# edition4-mainpart_1.net
KiCad netlist of a schematic drawn in EAGLE
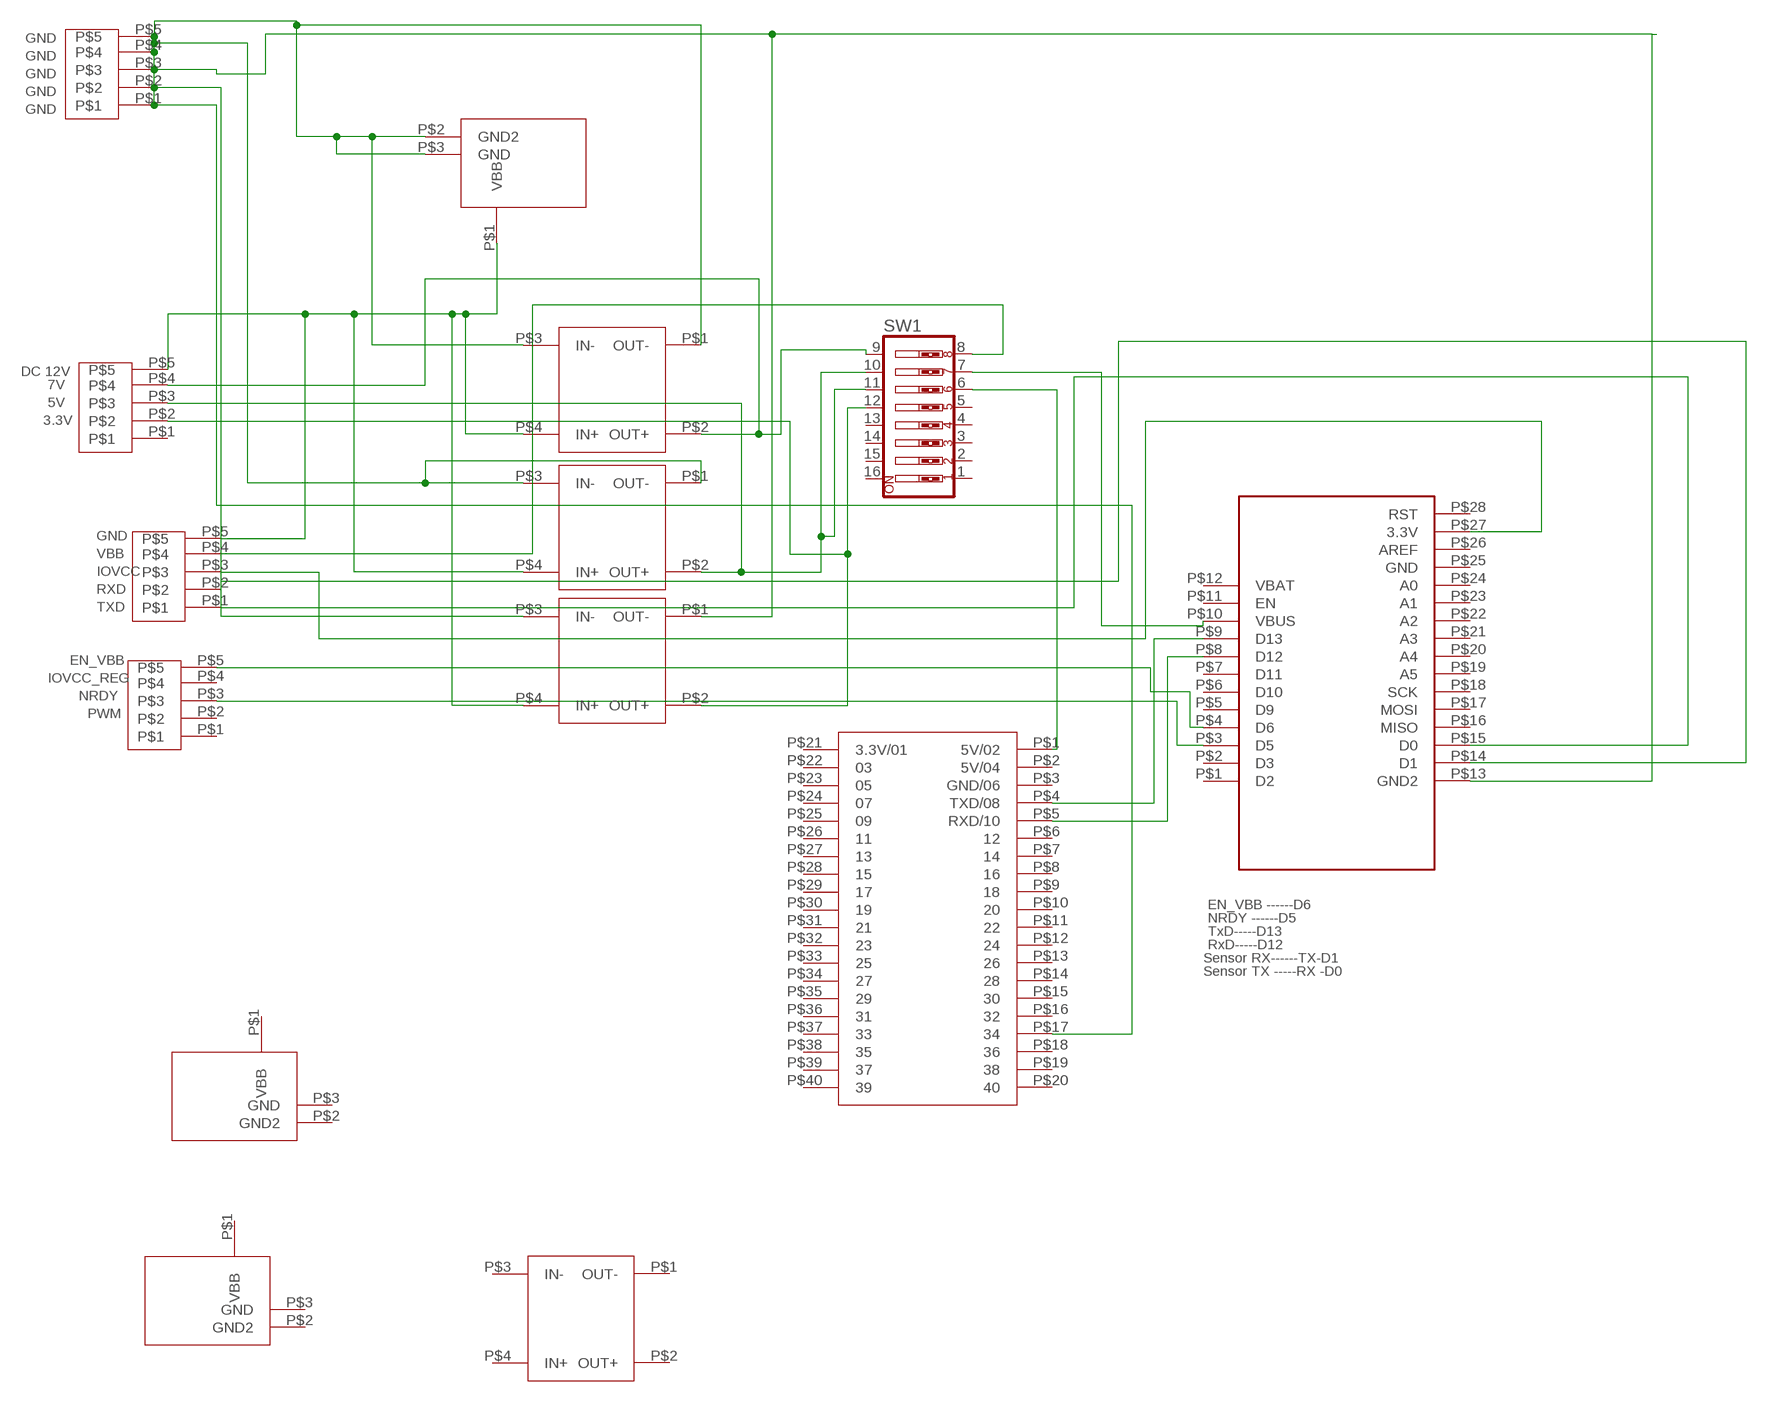
[diagram p0: schematic, sheet 1]

(export (version "E")
  (design (tool "Eeschema 10.0.6"))
  (components
    (comp (ref "SW1")
      (value "SW_DIP-8")
      (footprint "eagle-import:EDG-08")
      (libsource (lib "eagle-import") (part "SW_DIP-8"))
    )
    (comp (ref "U$1")
      (value "PIN")
      (footprint "eagle-import:PIN")
      (libsource (lib "eagle-import") (part "PIN"))
    )
    (comp (ref "U$2")
      (value "PIN")
      (footprint "eagle-import:PIN")
      (libsource (lib "eagle-import") (part "PIN"))
    )
    (comp (ref "U$3")
      (value "POWER")
      (footprint "eagle-import:POWERIN")
      (libsource (lib "eagle-import") (part "POWER"))
    )
    (comp (ref "U$4")
      (value "POWER")
      (footprint "eagle-import:POWERIN")
      (libsource (lib "eagle-import") (part "POWER"))
    )
    (comp (ref "U$5")
      (value "POWER")
      (footprint "eagle-import:POWERIN")
      (libsource (lib "eagle-import") (part "POWER"))
    )
    (comp (ref "U$6")
      (value "MH-MINI-360")
      (footprint "eagle-import:MH-MINI-360")
      (libsource (lib "eagle-import") (part "MH-MINI-360"))
    )
    (comp (ref "U$7")
      (value "MH-MINI-360")
      (footprint "eagle-import:MH-MINI-360")
      (libsource (lib "eagle-import") (part "MH-MINI-360"))
    )
    (comp (ref "U$8")
      (value "MH-MINI-360")
      (footprint "eagle-import:MH-MINI-360")
      (libsource (lib "eagle-import") (part "MH-MINI-360"))
    )
    (comp (ref "U$9")
      (value "MH-MINI-360")
      (footprint "eagle-import:MH-MINI-360")
      (libsource (lib "eagle-import") (part "MH-MINI-360"))
    )
    (comp (ref "U$10")
      (value "FEATHER")
      (footprint "eagle-import:FEATHER")
      (libsource (lib "eagle-import") (part "FEATHER"))
    )
    (comp (ref "U$11")
      (value "RASPBERRYPI")
      (footprint "eagle-import:RASPBERRYPI")
      (libsource (lib "eagle-import") (part "RASPBERRYPI"))
    )
    (comp (ref "U$12")
      (value "PIN")
      (footprint "eagle-import:PIN")
      (libsource (lib "eagle-import") (part "PIN"))
    )
    (comp (ref "U$13")
      (value "PIN")
      (footprint "eagle-import:PIN")
      (libsource (lib "eagle-import") (part "PIN"))
    )
  )
  (nets
    (net (code "1") (name "Net-(SW1-Pad8)") (class "Default")
      (node (ref "SW1") (pin "8") (pinfunction "8_8") (pintype "passive"))
      (node (ref "U$1") (pin "P$4") (pinfunction "P$4_P$4") (pintype "bidirectional"))
    )
    (net (code "2") (name "Net-(U$3-VBB)") (class "Default")
      (node (ref "U$1") (pin "P$5") (pinfunction "P$5_P$5") (pintype "bidirectional"))
      (node (ref "U$12") (pin "P$5") (pinfunction "P$5_P$5") (pintype "bidirectional"))
      (node (ref "U$3") (pin "P$1") (pinfunction "VBB_P$1") (pintype "bidirectional"))
      (node (ref "U$6") (pin "P$4") (pinfunction "IN+_P$4") (pintype "bidirectional"))
      (node (ref "U$8") (pin "P$4") (pinfunction "IN+_P$4") (pintype "bidirectional"))
      (node (ref "U$9") (pin "P$4") (pinfunction "IN+_P$4") (pintype "bidirectional"))
    )
    (net (code "3") (name "Net-(U$6-OUT+)") (class "Default")
      (node (ref "SW1") (pin "9") (pinfunction "9_9") (pintype "passive"))
      (node (ref "U$12") (pin "P$4") (pinfunction "P$4_P$4") (pintype "bidirectional"))
      (node (ref "U$6") (pin "P$2") (pinfunction "OUT+_P$2") (pintype "bidirectional"))
    )
    (net (code "4") (name "Net-(U$8-OUT+)") (class "Default")
      (node (ref "SW1") (pin "12") (pinfunction "12_12") (pintype "passive"))
      (node (ref "U$12") (pin "P$2") (pinfunction "P$2_P$2") (pintype "bidirectional"))
      (node (ref "U$8") (pin "P$2") (pinfunction "OUT+_P$2") (pintype "bidirectional"))
    )
    (net (code "5") (name "Net-(U$9-OUT+)") (class "Default")
      (node (ref "SW1") (pin "10") (pinfunction "10_10") (pintype "passive"))
      (node (ref "SW1") (pin "11") (pinfunction "11_11") (pintype "passive"))
      (node (ref "U$12") (pin "P$3") (pinfunction "P$3_P$3") (pintype "bidirectional"))
      (node (ref "U$9") (pin "P$2") (pinfunction "OUT+_P$2") (pintype "bidirectional"))
    )
    (net (code "6") (name "Net-(U$10-3.3V)") (class "Default")
      (node (ref "U$1") (pin "P$3") (pinfunction "P$3_P$3") (pintype "bidirectional"))
      (node (ref "U$10") (pin "P$27") (pinfunction "3.3V_P$27") (pintype "bidirectional"))
    )
    (net (code "7") (name "Net-(U$10-D0)") (class "Default")
      (node (ref "U$1") (pin "P$1") (pinfunction "P$1_P$1") (pintype "bidirectional"))
      (node (ref "U$10") (pin "P$15") (pinfunction "D0_P$15") (pintype "bidirectional"))
    )
    (net (code "8") (name "Net-(U$10-D1)") (class "Default")
      (node (ref "U$1") (pin "P$2") (pinfunction "P$2_P$2") (pintype "bidirectional"))
      (node (ref "U$10") (pin "P$14") (pinfunction "D1_P$14") (pintype "bidirectional"))
    )
    (net (code "9") (name "Net-(U$10-D5)") (class "Default")
      (node (ref "U$10") (pin "P$3") (pinfunction "D5_P$3") (pintype "bidirectional"))
      (node (ref "U$2") (pin "P$3") (pinfunction "P$3_P$3") (pintype "bidirectional"))
    )
    (net (code "10") (name "Net-(U$10-D6)") (class "Default")
      (node (ref "U$10") (pin "P$4") (pinfunction "D6_P$4") (pintype "bidirectional"))
      (node (ref "U$2") (pin "P$5") (pinfunction "P$5_P$5") (pintype "bidirectional"))
    )
    (net (code "11") (name "Net-(U$10-D12)") (class "Default")
      (node (ref "U$10") (pin "P$8") (pinfunction "D12_P$8") (pintype "bidirectional"))
      (node (ref "U$11") (pin "P$5") (pinfunction "RXD/10_P$5") (pintype "bidirectional"))
    )
    (net (code "12") (name "Net-(U$10-D13)") (class "Default")
      (node (ref "U$10") (pin "P$9") (pinfunction "D13_P$9") (pintype "bidirectional"))
      (node (ref "U$11") (pin "P$4") (pinfunction "TXD/08_P$4") (pintype "bidirectional"))
    )
    (net (code "13") (name "Net-(U$10-GND2)") (class "Default")
      (node (ref "U$10") (pin "P$13") (pinfunction "GND2_P$13") (pintype "bidirectional"))
      (node (ref "U$11") (pin "P$17") (pinfunction "34_P$17") (pintype "bidirectional"))
      (node (ref "U$13") (pin "P$1") (pinfunction "P$1_P$1") (pintype "bidirectional"))
      (node (ref "U$13") (pin "P$2") (pinfunction "P$2_P$2") (pintype "bidirectional"))
      (node (ref "U$13") (pin "P$3") (pinfunction "P$3_P$3") (pintype "bidirectional"))
      (node (ref "U$13") (pin "P$4") (pinfunction "P$4_P$4") (pintype "bidirectional"))
      (node (ref "U$13") (pin "P$5") (pinfunction "P$5_P$5") (pintype "bidirectional"))
      (node (ref "U$3") (pin "P$2") (pinfunction "GND2_P$2") (pintype "bidirectional"))
      (node (ref "U$3") (pin "P$3") (pinfunction "GND_P$3") (pintype "bidirectional"))
      (node (ref "U$6") (pin "P$1") (pinfunction "OUT-_P$1") (pintype "bidirectional"))
      (node (ref "U$6") (pin "P$3") (pinfunction "IN-_P$3") (pintype "bidirectional"))
      (node (ref "U$8") (pin "P$1") (pinfunction "OUT-_P$1") (pintype "bidirectional"))
      (node (ref "U$8") (pin "P$3") (pinfunction "IN-_P$3") (pintype "bidirectional"))
      (node (ref "U$9") (pin "P$1") (pinfunction "OUT-_P$1") (pintype "bidirectional"))
      (node (ref "U$9") (pin "P$3") (pinfunction "IN-_P$3") (pintype "bidirectional"))
    )
    (net (code "14") (name "Net-(U$10-VBUS)") (class "Default")
      (node (ref "SW1") (pin "7") (pinfunction "7_7") (pintype "passive"))
      (node (ref "U$10") (pin "P$10") (pinfunction "VBUS_P$10") (pintype "bidirectional"))
    )
    (net (code "15") (name "Net-(U$11-5V{slash}02)") (class "Default")
      (node (ref "SW1") (pin "6") (pinfunction "6_6") (pintype "passive"))
      (node (ref "U$11") (pin "P$1") (pinfunction "5V/02_P$1") (pintype "bidirectional"))
    )
    (net (code "16") (name "unconnected-(SW1-Pad1)") (class "Default")
      (node (ref "SW1") (pin "1") (pinfunction "1_1") (pintype "passive"))
    )
    (net (code "17") (name "unconnected-(SW1-Pad2)") (class "Default")
      (node (ref "SW1") (pin "2") (pinfunction "2_2") (pintype "passive"))
    )
    (net (code "18") (name "unconnected-(SW1-Pad3)") (class "Default")
      (node (ref "SW1") (pin "3") (pinfunction "3_3") (pintype "passive"))
    )
    (net (code "19") (name "unconnected-(SW1-Pad4)") (class "Default")
      (node (ref "SW1") (pin "4") (pinfunction "4_4") (pintype "passive"))
    )
    (net (code "20") (name "unconnected-(SW1-Pad5)") (class "Default")
      (node (ref "SW1") (pin "5") (pinfunction "5_5") (pintype "passive"))
    )
    (net (code "21") (name "unconnected-(SW1-Pad13)") (class "Default")
      (node (ref "SW1") (pin "13") (pinfunction "13_13") (pintype "passive"))
    )
    (net (code "22") (name "unconnected-(SW1-Pad14)") (class "Default")
      (node (ref "SW1") (pin "14") (pinfunction "14_14") (pintype "passive"))
    )
    (net (code "23") (name "unconnected-(SW1-Pad15)") (class "Default")
      (node (ref "SW1") (pin "15") (pinfunction "15_15") (pintype "passive"))
    )
    (net (code "24") (name "unconnected-(SW1-Pad16)") (class "Default")
      (node (ref "SW1") (pin "16") (pinfunction "16_16") (pintype "passive"))
    )
    (net (code "25") (name "unconnected-(U$2-PadP$1)") (class "Default")
      (node (ref "U$2") (pin "P$1") (pinfunction "P$1_P$1") (pintype "bidirectional"))
    )
    (net (code "26") (name "unconnected-(U$2-PadP$2)") (class "Default")
      (node (ref "U$2") (pin "P$2") (pinfunction "P$2_P$2") (pintype "bidirectional"))
    )
    (net (code "27") (name "unconnected-(U$2-PadP$4)") (class "Default")
      (node (ref "U$2") (pin "P$4") (pinfunction "P$4_P$4") (pintype "bidirectional"))
    )
    (net (code "28") (name "unconnected-(U$4-GND-PadP$3)") (class "Default")
      (node (ref "U$4") (pin "P$3") (pinfunction "GND_P$3") (pintype "bidirectional"))
    )
    (net (code "29") (name "unconnected-(U$4-GND2-PadP$2)") (class "Default")
      (node (ref "U$4") (pin "P$2") (pinfunction "GND2_P$2") (pintype "bidirectional"))
    )
    (net (code "30") (name "unconnected-(U$4-VBB-PadP$1)") (class "Default")
      (node (ref "U$4") (pin "P$1") (pinfunction "VBB_P$1") (pintype "bidirectional"))
    )
    (net (code "31") (name "unconnected-(U$5-GND-PadP$3)") (class "Default")
      (node (ref "U$5") (pin "P$3") (pinfunction "GND_P$3") (pintype "bidirectional"))
    )
    (net (code "32") (name "unconnected-(U$5-GND2-PadP$2)") (class "Default")
      (node (ref "U$5") (pin "P$2") (pinfunction "GND2_P$2") (pintype "bidirectional"))
    )
    (net (code "33") (name "unconnected-(U$5-VBB-PadP$1)") (class "Default")
      (node (ref "U$5") (pin "P$1") (pinfunction "VBB_P$1") (pintype "bidirectional"))
    )
    (net (code "34") (name "unconnected-(U$7-IN+-PadP$4)") (class "Default")
      (node (ref "U$7") (pin "P$4") (pinfunction "IN+_P$4") (pintype "bidirectional"))
    )
    (net (code "35") (name "unconnected-(U$7-IN--PadP$3)") (class "Default")
      (node (ref "U$7") (pin "P$3") (pinfunction "IN-_P$3") (pintype "bidirectional"))
    )
    (net (code "36") (name "unconnected-(U$7-OUT+-PadP$2)") (class "Default")
      (node (ref "U$7") (pin "P$2") (pinfunction "OUT+_P$2") (pintype "bidirectional"))
    )
    (net (code "37") (name "unconnected-(U$7-OUT--PadP$1)") (class "Default")
      (node (ref "U$7") (pin "P$1") (pinfunction "OUT-_P$1") (pintype "bidirectional"))
    )
    (net (code "38") (name "unconnected-(U$10-A0-PadP$24)") (class "Default")
      (node (ref "U$10") (pin "P$24") (pinfunction "A0_P$24") (pintype "bidirectional"))
    )
    (net (code "39") (name "unconnected-(U$10-A1-PadP$23)") (class "Default")
      (node (ref "U$10") (pin "P$23") (pinfunction "A1_P$23") (pintype "bidirectional"))
    )
    (net (code "40") (name "unconnected-(U$10-A2-PadP$22)") (class "Default")
      (node (ref "U$10") (pin "P$22") (pinfunction "A2_P$22") (pintype "bidirectional"))
    )
    (net (code "41") (name "unconnected-(U$10-A3-PadP$21)") (class "Default")
      (node (ref "U$10") (pin "P$21") (pinfunction "A3_P$21") (pintype "bidirectional"))
    )
    (net (code "42") (name "unconnected-(U$10-A4-PadP$20)") (class "Default")
      (node (ref "U$10") (pin "P$20") (pinfunction "A4_P$20") (pintype "bidirectional"))
    )
    (net (code "43") (name "unconnected-(U$10-A5-PadP$19)") (class "Default")
      (node (ref "U$10") (pin "P$19") (pinfunction "A5_P$19") (pintype "bidirectional"))
    )
    (net (code "44") (name "unconnected-(U$10-AREF-PadP$26)") (class "Default")
      (node (ref "U$10") (pin "P$26") (pinfunction "AREF_P$26") (pintype "bidirectional"))
    )
    (net (code "45") (name "unconnected-(U$10-D2-PadP$1)") (class "Default")
      (node (ref "U$10") (pin "P$1") (pinfunction "D2_P$1") (pintype "bidirectional"))
    )
    (net (code "46") (name "unconnected-(U$10-D3-PadP$2)") (class "Default")
      (node (ref "U$10") (pin "P$2") (pinfunction "D3_P$2") (pintype "bidirectional"))
    )
    (net (code "47") (name "unconnected-(U$10-D9-PadP$5)") (class "Default")
      (node (ref "U$10") (pin "P$5") (pinfunction "D9_P$5") (pintype "bidirectional"))
    )
    (net (code "48") (name "unconnected-(U$10-D10-PadP$6)") (class "Default")
      (node (ref "U$10") (pin "P$6") (pinfunction "D10_P$6") (pintype "bidirectional"))
    )
    (net (code "49") (name "unconnected-(U$10-D11-PadP$7)") (class "Default")
      (node (ref "U$10") (pin "P$7") (pinfunction "D11_P$7") (pintype "bidirectional"))
    )
    (net (code "50") (name "unconnected-(U$10-EN-PadP$11)") (class "Default")
      (node (ref "U$10") (pin "P$11") (pinfunction "EN_P$11") (pintype "bidirectional"))
    )
    (net (code "51") (name "unconnected-(U$10-GND-PadP$25)") (class "Default")
      (node (ref "U$10") (pin "P$25") (pinfunction "GND_P$25") (pintype "bidirectional"))
    )
    (net (code "52") (name "unconnected-(U$10-MISO-PadP$16)") (class "Default")
      (node (ref "U$10") (pin "P$16") (pinfunction "MISO_P$16") (pintype "bidirectional"))
    )
    (net (code "53") (name "unconnected-(U$10-MOSI-PadP$17)") (class "Default")
      (node (ref "U$10") (pin "P$17") (pinfunction "MOSI_P$17") (pintype "bidirectional"))
    )
    (net (code "54") (name "unconnected-(U$10-RST-PadP$28)") (class "Default")
      (node (ref "U$10") (pin "P$28") (pinfunction "RST_P$28") (pintype "bidirectional"))
    )
    (net (code "55") (name "unconnected-(U$10-SCK-PadP$18)") (class "Default")
      (node (ref "U$10") (pin "P$18") (pinfunction "SCK_P$18") (pintype "bidirectional"))
    )
    (net (code "56") (name "unconnected-(U$10-VBAT-PadP$12)") (class "Default")
      (node (ref "U$10") (pin "P$12") (pinfunction "VBAT_P$12") (pintype "bidirectional"))
    )
    (net (code "57") (name "unconnected-(U$11-03-PadP$22)") (class "Default")
      (node (ref "U$11") (pin "P$22") (pinfunction "03_P$22") (pintype "bidirectional"))
    )
    (net (code "58") (name "unconnected-(U$11-3.3V{slash}01-PadP$21)") (class "Default")
      (node (ref "U$11") (pin "P$21") (pinfunction "3.3V/01_P$21") (pintype "bidirectional"))
    )
    (net (code "59") (name "unconnected-(U$11-05-PadP$23)") (class "Default")
      (node (ref "U$11") (pin "P$23") (pinfunction "05_P$23") (pintype "bidirectional"))
    )
    (net (code "60") (name "unconnected-(U$11-5V{slash}04-PadP$2)") (class "Default")
      (node (ref "U$11") (pin "P$2") (pinfunction "5V/04_P$2") (pintype "bidirectional"))
    )
    (net (code "61") (name "unconnected-(U$11-07-PadP$24)") (class "Default")
      (node (ref "U$11") (pin "P$24") (pinfunction "07_P$24") (pintype "bidirectional"))
    )
    (net (code "62") (name "unconnected-(U$11-09-PadP$25)") (class "Default")
      (node (ref "U$11") (pin "P$25") (pinfunction "09_P$25") (pintype "bidirectional"))
    )
    (net (code "63") (name "unconnected-(U$11-11-PadP$26)") (class "Default")
      (node (ref "U$11") (pin "P$26") (pinfunction "11_P$26") (pintype "bidirectional"))
    )
    (net (code "64") (name "unconnected-(U$11-12-PadP$6)") (class "Default")
      (node (ref "U$11") (pin "P$6") (pinfunction "12_P$6") (pintype "bidirectional"))
    )
    (net (code "65") (name "unconnected-(U$11-13-PadP$27)") (class "Default")
      (node (ref "U$11") (pin "P$27") (pinfunction "13_P$27") (pintype "bidirectional"))
    )
    (net (code "66") (name "unconnected-(U$11-14-PadP$7)") (class "Default")
      (node (ref "U$11") (pin "P$7") (pinfunction "14_P$7") (pintype "bidirectional"))
    )
    (net (code "67") (name "unconnected-(U$11-15-PadP$28)") (class "Default")
      (node (ref "U$11") (pin "P$28") (pinfunction "15_P$28") (pintype "bidirectional"))
    )
    (net (code "68") (name "unconnected-(U$11-16-PadP$8)") (class "Default")
      (node (ref "U$11") (pin "P$8") (pinfunction "16_P$8") (pintype "bidirectional"))
    )
    (net (code "69") (name "unconnected-(U$11-17-PadP$29)") (class "Default")
      (node (ref "U$11") (pin "P$29") (pinfunction "17_P$29") (pintype "bidirectional"))
    )
    (net (code "70") (name "unconnected-(U$11-18-PadP$9)") (class "Default")
      (node (ref "U$11") (pin "P$9") (pinfunction "18_P$9") (pintype "bidirectional"))
    )
    (net (code "71") (name "unconnected-(U$11-19-PadP$30)") (class "Default")
      (node (ref "U$11") (pin "P$30") (pinfunction "19_P$30") (pintype "bidirectional"))
    )
    (net (code "72") (name "unconnected-(U$11-20-PadP$10)") (class "Default")
      (node (ref "U$11") (pin "P$10") (pinfunction "20_P$10") (pintype "bidirectional"))
    )
    (net (code "73") (name "unconnected-(U$11-21-PadP$31)") (class "Default")
      (node (ref "U$11") (pin "P$31") (pinfunction "21_P$31") (pintype "bidirectional"))
    )
    (net (code "74") (name "unconnected-(U$11-22-PadP$11)") (class "Default")
      (node (ref "U$11") (pin "P$11") (pinfunction "22_P$11") (pintype "bidirectional"))
    )
    (net (code "75") (name "unconnected-(U$11-23-PadP$32)") (class "Default")
      (node (ref "U$11") (pin "P$32") (pinfunction "23_P$32") (pintype "bidirectional"))
    )
    (net (code "76") (name "unconnected-(U$11-24-PadP$12)") (class "Default")
      (node (ref "U$11") (pin "P$12") (pinfunction "24_P$12") (pintype "bidirectional"))
    )
    (net (code "77") (name "unconnected-(U$11-25-PadP$33)") (class "Default")
      (node (ref "U$11") (pin "P$33") (pinfunction "25_P$33") (pintype "bidirectional"))
    )
    (net (code "78") (name "unconnected-(U$11-26-PadP$13)") (class "Default")
      (node (ref "U$11") (pin "P$13") (pinfunction "26_P$13") (pintype "bidirectional"))
    )
    (net (code "79") (name "unconnected-(U$11-27-PadP$34)") (class "Default")
      (node (ref "U$11") (pin "P$34") (pinfunction "27_P$34") (pintype "bidirectional"))
    )
    (net (code "80") (name "unconnected-(U$11-28-PadP$14)") (class "Default")
      (node (ref "U$11") (pin "P$14") (pinfunction "28_P$14") (pintype "bidirectional"))
    )
    (net (code "81") (name "unconnected-(U$11-29-PadP$35)") (class "Default")
      (node (ref "U$11") (pin "P$35") (pinfunction "29_P$35") (pintype "bidirectional"))
    )
    (net (code "82") (name "unconnected-(U$11-30-PadP$15)") (class "Default")
      (node (ref "U$11") (pin "P$15") (pinfunction "30_P$15") (pintype "bidirectional"))
    )
    (net (code "83") (name "unconnected-(U$11-31-PadP$36)") (class "Default")
      (node (ref "U$11") (pin "P$36") (pinfunction "31_P$36") (pintype "bidirectional"))
    )
    (net (code "84") (name "unconnected-(U$11-32-PadP$16)") (class "Default")
      (node (ref "U$11") (pin "P$16") (pinfunction "32_P$16") (pintype "bidirectional"))
    )
    (net (code "85") (name "unconnected-(U$11-33-PadP$37)") (class "Default")
      (node (ref "U$11") (pin "P$37") (pinfunction "33_P$37") (pintype "bidirectional"))
    )
    (net (code "86") (name "unconnected-(U$11-35-PadP$38)") (class "Default")
      (node (ref "U$11") (pin "P$38") (pinfunction "35_P$38") (pintype "bidirectional"))
    )
    (net (code "87") (name "unconnected-(U$11-36-PadP$18)") (class "Default")
      (node (ref "U$11") (pin "P$18") (pinfunction "36_P$18") (pintype "bidirectional"))
    )
    (net (code "88") (name "unconnected-(U$11-37-PadP$39)") (class "Default")
      (node (ref "U$11") (pin "P$39") (pinfunction "37_P$39") (pintype "bidirectional"))
    )
    (net (code "89") (name "unconnected-(U$11-38-PadP$19)") (class "Default")
      (node (ref "U$11") (pin "P$19") (pinfunction "38_P$19") (pintype "bidirectional"))
    )
    (net (code "90") (name "unconnected-(U$11-39-PadP$40)") (class "Default")
      (node (ref "U$11") (pin "P$40") (pinfunction "39_P$40") (pintype "bidirectional"))
    )
    (net (code "91") (name "unconnected-(U$11-40-PadP$20)") (class "Default")
      (node (ref "U$11") (pin "P$20") (pinfunction "40_P$20") (pintype "bidirectional"))
    )
    (net (code "92") (name "unconnected-(U$11-GND{slash}06-PadP$3)") (class "Default")
      (node (ref "U$11") (pin "P$3") (pinfunction "GND/06_P$3") (pintype "bidirectional"))
    )
    (net (code "93") (name "unconnected-(U$12-PadP$1)") (class "Default")
      (node (ref "U$12") (pin "P$1") (pinfunction "P$1_P$1") (pintype "bidirectional"))
    )
  )
)
